# twopropmixtiny.net
KiCad netlist of a schematic drawn in EAGLE
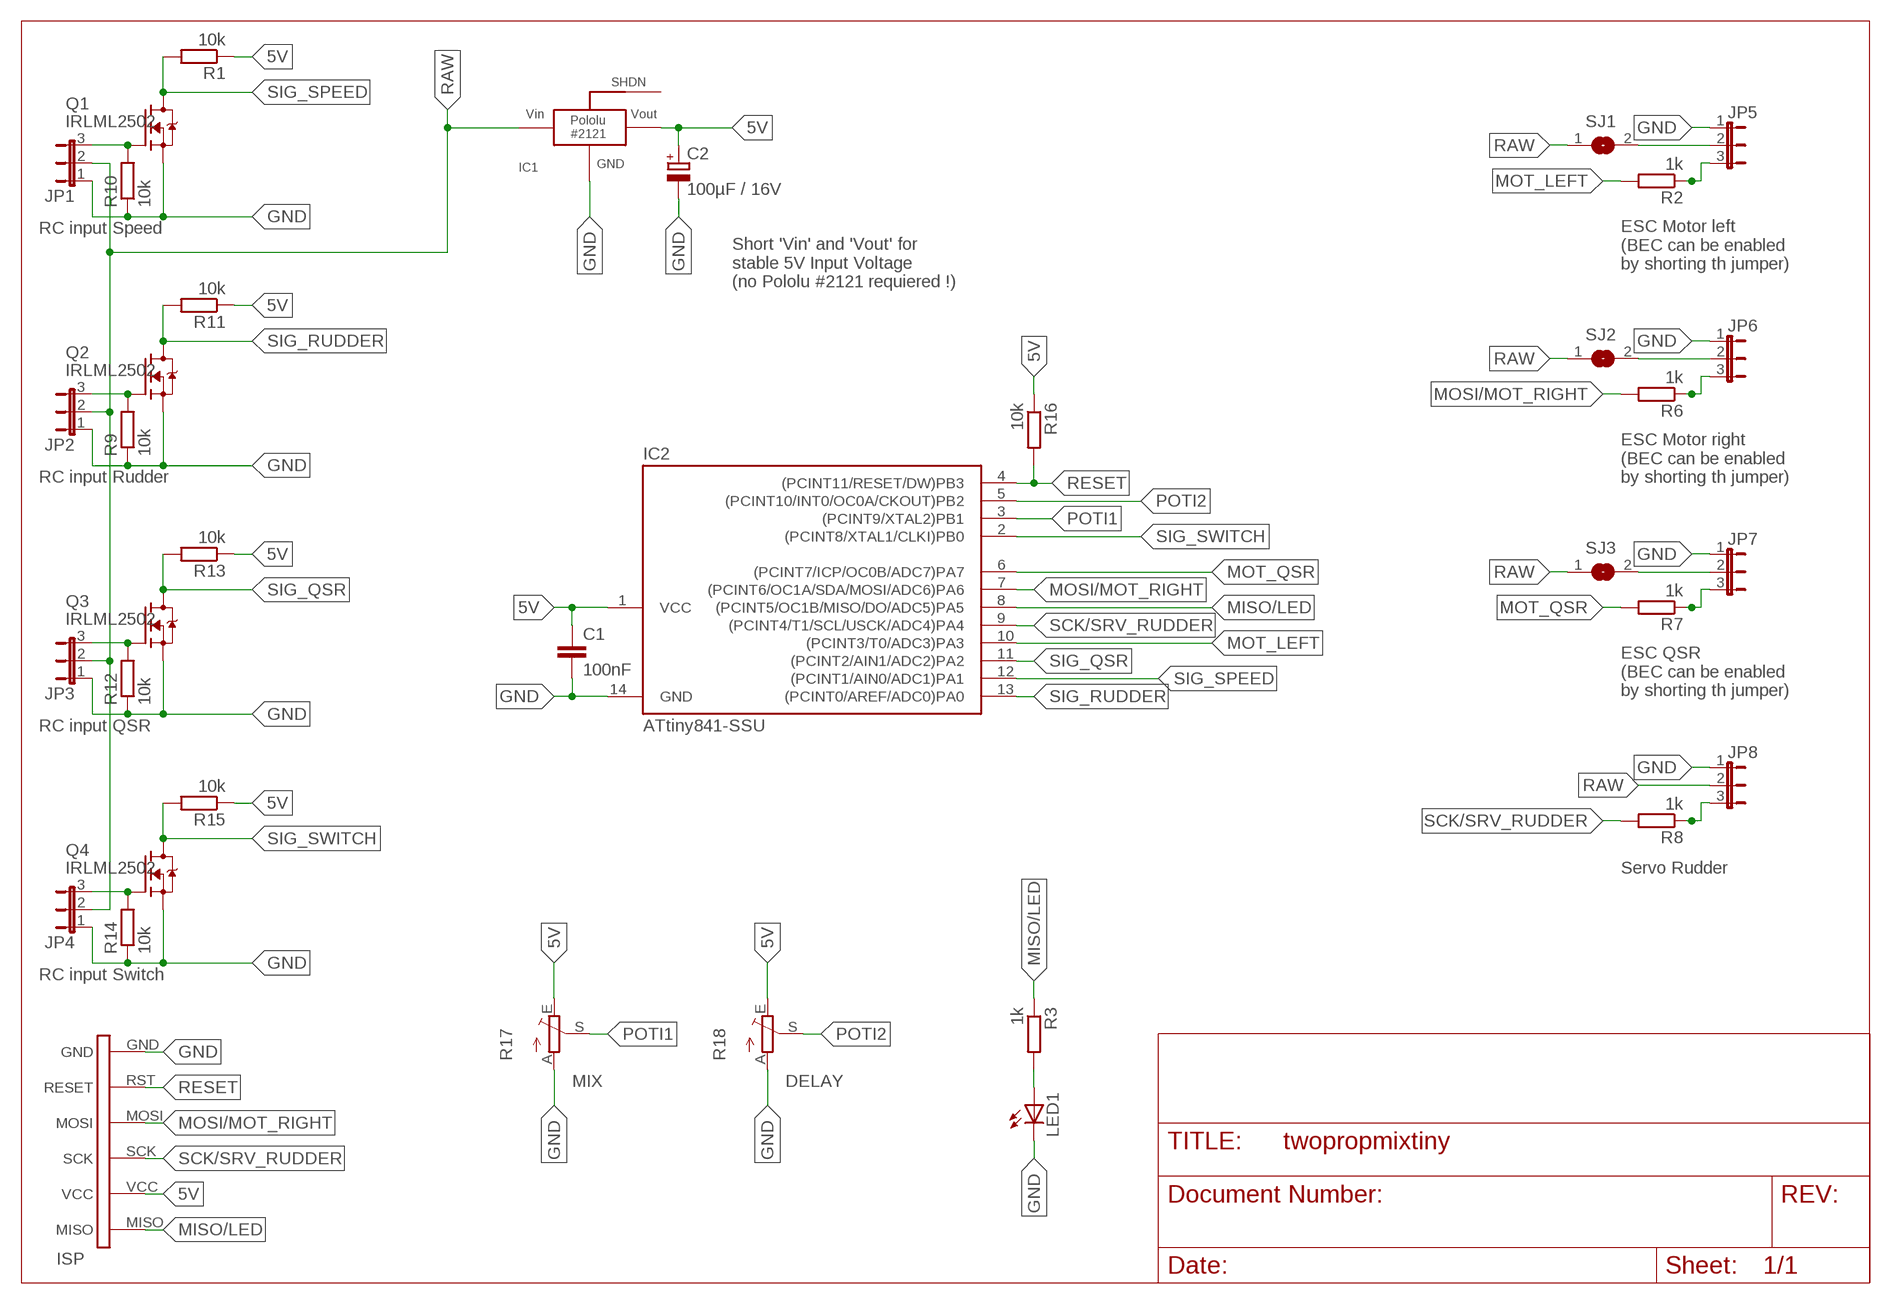
[diagram p0: schematic, sheet 1]

(export (version "E")
  (design (tool "Eeschema 10.0.6"))
  (components
    (comp (ref "C1")
      (value "100nF")
      (footprint "eagle-import:C0805")
      (libsource (lib "eagle-import") (part "C-EUC0805"))
    )
    (comp (ref "C2")
      (value "100µF / 16V")
      (footprint "eagle-import:PANASONIC_D")
      (libsource (lib "eagle-import") (part "CPOL-EUD"))
    )
    (comp (ref "IC1")
      (value "POLOLU2121")
      (footprint "eagle-import:POLOLU2121")
      (libsource (lib "eagle-import") (part "POLOLU2121"))
    )
    (comp (ref "IC2")
      (value "ATtiny841-SSU")
      (footprint "eagle-import:SOIC14")
      (libsource (lib "eagle-import") (part "TINY24/44/84-SSU"))
    )
    (comp (ref "JP1")
      (value "JP2EJP2_OHNE_TEXT")
      (footprint "eagle-import:JP2")
      (libsource (lib "eagle-import") (part "JP2EJP2_OHNE_TEXT"))
    )
    (comp (ref "JP2")
      (value "JP2EJP2_OHNE_TEXT")
      (footprint "eagle-import:JP2")
      (libsource (lib "eagle-import") (part "JP2EJP2_OHNE_TEXT"))
    )
    (comp (ref "JP3")
      (value "JP2EJP2_OHNE_TEXT")
      (footprint "eagle-import:JP2")
      (libsource (lib "eagle-import") (part "JP2EJP2_OHNE_TEXT"))
    )
    (comp (ref "JP4")
      (value "JP2EJP2_OHNE_TEXT")
      (footprint "eagle-import:JP2")
      (libsource (lib "eagle-import") (part "JP2EJP2_OHNE_TEXT"))
    )
    (comp (ref "JP5")
      (value "JP2EJP2_OHNE_TEXT")
      (footprint "eagle-import:JP2")
      (libsource (lib "eagle-import") (part "JP2EJP2_OHNE_TEXT"))
    )
    (comp (ref "JP6")
      (value "JP2EJP2_OHNE_TEXT")
      (footprint "eagle-import:JP2")
      (libsource (lib "eagle-import") (part "JP2EJP2_OHNE_TEXT"))
    )
    (comp (ref "JP7")
      (value "JP2EJP2_OHNE_TEXT")
      (footprint "eagle-import:JP2")
      (libsource (lib "eagle-import") (part "JP2EJP2_OHNE_TEXT"))
    )
    (comp (ref "JP8")
      (value "JP2EJP2_OHNE_TEXT")
      (footprint "eagle-import:JP2")
      (libsource (lib "eagle-import") (part "JP2EJP2_OHNE_TEXT"))
    )
    (comp (ref "LED1")
      (value "LEDCHIPLED_0805")
      (footprint "eagle-import:CHIPLED_0805")
      (libsource (lib "eagle-import") (part "LEDCHIPLED_0805"))
    )
    (comp (ref "Q1")
      (value "IRLML2502")
      (footprint "eagle-import:SOT23-3")
      (libsource (lib "eagle-import") (part "IRLML2502"))
    )
    (comp (ref "Q2")
      (value "IRLML2502")
      (footprint "eagle-import:SOT23-3")
      (libsource (lib "eagle-import") (part "IRLML2502"))
    )
    (comp (ref "Q3")
      (value "IRLML2502")
      (footprint "eagle-import:SOT23-3")
      (libsource (lib "eagle-import") (part "IRLML2502"))
    )
    (comp (ref "Q4")
      (value "IRLML2502")
      (footprint "eagle-import:SOT23-3")
      (libsource (lib "eagle-import") (part "IRLML2502"))
    )
    (comp (ref "R1")
      (value "10k")
      (footprint "eagle-import:R0805")
      (libsource (lib "eagle-import") (part "R-EU_R0805"))
    )
    (comp (ref "R2")
      (value "1k")
      (footprint "eagle-import:R0805")
      (libsource (lib "eagle-import") (part "R-EU_R0805"))
    )
    (comp (ref "R3")
      (value "1k")
      (footprint "eagle-import:R0805")
      (libsource (lib "eagle-import") (part "R-EU_R0805"))
    )
    (comp (ref "R6")
      (value "1k")
      (footprint "eagle-import:R0805")
      (libsource (lib "eagle-import") (part "R-EU_R0805"))
    )
    (comp (ref "R7")
      (value "1k")
      (footprint "eagle-import:R0805")
      (libsource (lib "eagle-import") (part "R-EU_R0805"))
    )
    (comp (ref "R8")
      (value "1k")
      (footprint "eagle-import:R0805")
      (libsource (lib "eagle-import") (part "R-EU_R0805"))
    )
    (comp (ref "R9")
      (value "10k")
      (footprint "eagle-import:R0805")
      (libsource (lib "eagle-import") (part "R-EU_R0805"))
    )
    (comp (ref "R10")
      (value "10k")
      (footprint "eagle-import:R0805")
      (libsource (lib "eagle-import") (part "R-EU_R0805"))
    )
    (comp (ref "R11")
      (value "10k")
      (footprint "eagle-import:R0805")
      (libsource (lib "eagle-import") (part "R-EU_R0805"))
    )
    (comp (ref "R12")
      (value "10k")
      (footprint "eagle-import:R0805")
      (libsource (lib "eagle-import") (part "R-EU_R0805"))
    )
    (comp (ref "R13")
      (value "10k")
      (footprint "eagle-import:R0805")
      (libsource (lib "eagle-import") (part "R-EU_R0805"))
    )
    (comp (ref "R14")
      (value "10k")
      (footprint "eagle-import:R0805")
      (libsource (lib "eagle-import") (part "R-EU_R0805"))
    )
    (comp (ref "R15")
      (value "10k")
      (footprint "eagle-import:R0805")
      (libsource (lib "eagle-import") (part "R-EU_R0805"))
    )
    (comp (ref "R16")
      (value "10k")
      (footprint "eagle-import:R0805")
      (libsource (lib "eagle-import") (part "R-EU_R0805"))
    )
    (comp (ref "R17")
      (value "TRIM_EU-PT10")
      (footprint "eagle-import:PT-10")
      (libsource (lib "eagle-import") (part "TRIM_EU-PT10"))
    )
    (comp (ref "R18")
      (value "TRIM_EU-PT10")
      (footprint "eagle-import:PT-10")
      (libsource (lib "eagle-import") (part "TRIM_EU-PT10"))
    )
    (comp (ref "SJ1") (value "SJ") (footprint "eagle-import:SJ") (libsource (lib "eagle-import") (part "SJ")))
    (comp (ref "SJ2") (value "SJ") (footprint "eagle-import:SJ") (libsource (lib "eagle-import") (part "SJ")))
    (comp (ref "SJ3") (value "SJ") (footprint "eagle-import:SJ") (libsource (lib "eagle-import") (part "SJ")))
    (comp (ref "U$1")
      (value "ISP")
      (footprint "eagle-import:ISP")
      (libsource (lib "eagle-import") (part "ISP"))
    )
  )
  (nets
    (net (code "1") (name "5V") (class "Default")
      (node (ref "C1") (pin "1") (pinfunction "1_1") (pintype "passive"))
      (node (ref "C2") (pin "+") (pinfunction "+_+") (pintype "passive"))
      (node (ref "IC1") (pin "VOUT") (pinfunction "VOUT_VOUT") (pintype "bidirectional"))
      (node (ref "IC2") (pin "1") (pinfunction "VCC_1") (pintype "power_in"))
      (node (ref "R1") (pin "1") (pinfunction "1_1") (pintype "passive"))
      (node (ref "R11") (pin "1") (pinfunction "1_1") (pintype "passive"))
      (node (ref "R13") (pin "1") (pinfunction "1_1") (pintype "passive"))
      (node (ref "R15") (pin "1") (pinfunction "1_1") (pintype "passive"))
      (node (ref "R16") (pin "1") (pinfunction "1_1") (pintype "passive"))
      (node (ref "R17") (pin "E") (pinfunction "E_E") (pintype "passive"))
      (node (ref "R18") (pin "E") (pinfunction "E_E") (pintype "passive"))
      (node (ref "U$1") (pin "VCC") (pinfunction "VCC_VCC") (pintype "bidirectional"))
    )
    (net (code "2") (name "GND") (class "Default")
      (node (ref "C1") (pin "2") (pinfunction "2_2") (pintype "passive"))
      (node (ref "C2") (pin "-") (pinfunction "-_-") (pintype "passive"))
      (node (ref "IC1") (pin "GND") (pinfunction "GND_GND") (pintype "bidirectional"))
      (node (ref "IC2") (pin "14") (pinfunction "GND_14") (pintype "power_in"))
      (node (ref "JP1") (pin "1") (pinfunction "1_1") (pintype "passive"))
      (node (ref "JP2") (pin "1") (pinfunction "1_1") (pintype "passive"))
      (node (ref "JP3") (pin "1") (pinfunction "1_1") (pintype "passive"))
      (node (ref "JP4") (pin "1") (pinfunction "1_1") (pintype "passive"))
      (node (ref "JP5") (pin "1") (pinfunction "1_1") (pintype "passive"))
      (node (ref "JP6") (pin "1") (pinfunction "1_1") (pintype "passive"))
      (node (ref "JP7") (pin "1") (pinfunction "1_1") (pintype "passive"))
      (node (ref "JP8") (pin "1") (pinfunction "1_1") (pintype "passive"))
      (node (ref "LED1") (pin "C") (pinfunction "C_C") (pintype "passive"))
      (node (ref "Q1") (pin "2") (pinfunction "S_2") (pintype "passive"))
      (node (ref "Q2") (pin "2") (pinfunction "S_2") (pintype "passive"))
      (node (ref "Q3") (pin "2") (pinfunction "S_2") (pintype "passive"))
      (node (ref "Q4") (pin "2") (pinfunction "S_2") (pintype "passive"))
      (node (ref "R10") (pin "1") (pinfunction "1_1") (pintype "passive"))
      (node (ref "R12") (pin "1") (pinfunction "1_1") (pintype "passive"))
      (node (ref "R14") (pin "1") (pinfunction "1_1") (pintype "passive"))
      (node (ref "R17") (pin "A") (pinfunction "A_A") (pintype "passive"))
      (node (ref "R18") (pin "A") (pinfunction "A_A") (pintype "passive"))
      (node (ref "R9") (pin "1") (pinfunction "1_1") (pintype "passive"))
      (node (ref "U$1") (pin "GND") (pinfunction "GND_GND") (pintype "bidirectional"))
    )
    (net (code "3") (name "MISO{slash}LED") (class "Default")
      (node (ref "IC2") (pin "8") (pinfunction "(PCINT5/OC1B/MISO/DO/ADC5)PA5_8") (pintype "bidirectional"))
      (node (ref "R3") (pin "1") (pinfunction "1_1") (pintype "passive"))
      (node (ref "U$1") (pin "MISO") (pinfunction "MISO_MISO") (pintype "bidirectional"))
    )
    (net (code "4") (name "MOSI{slash}MOT_RIGHT") (class "Default")
      (node (ref "IC2") (pin "7") (pinfunction "(PCINT6/OC1A/SDA/MOSI/ADC6)PA6_7") (pintype "bidirectional"))
      (node (ref "R6") (pin "2") (pinfunction "2_2") (pintype "passive"))
      (node (ref "U$1") (pin "MOSI") (pinfunction "MOSI_MOSI") (pintype "bidirectional"))
    )
    (net (code "5") (name "MOT_LEFT") (class "Default")
      (node (ref "IC2") (pin "10") (pinfunction "(PCINT3/T0/ADC3)PA3_10") (pintype "bidirectional"))
      (node (ref "R2") (pin "2") (pinfunction "2_2") (pintype "passive"))
    )
    (net (code "6") (name "MOT_QSR") (class "Default")
      (node (ref "IC2") (pin "6") (pinfunction "(PCINT7/ICP/OC0B/ADC7)PA7_6") (pintype "bidirectional"))
      (node (ref "R7") (pin "2") (pinfunction "2_2") (pintype "passive"))
    )
    (net (code "7") (name "Net-(JP5-Pad2)") (class "Default")
      (node (ref "JP5") (pin "2") (pinfunction "2_2") (pintype "passive"))
      (node (ref "SJ1") (pin "2") (pinfunction "2_2") (pintype "passive"))
    )
    (net (code "8") (name "Net-(JP5-Pad3)") (class "Default")
      (node (ref "JP5") (pin "3") (pinfunction "3_3") (pintype "passive"))
      (node (ref "R2") (pin "1") (pinfunction "1_1") (pintype "passive"))
    )
    (net (code "9") (name "Net-(JP6-Pad2)") (class "Default")
      (node (ref "JP6") (pin "2") (pinfunction "2_2") (pintype "passive"))
      (node (ref "SJ2") (pin "2") (pinfunction "2_2") (pintype "passive"))
    )
    (net (code "10") (name "Net-(JP6-Pad3)") (class "Default")
      (node (ref "JP6") (pin "3") (pinfunction "3_3") (pintype "passive"))
      (node (ref "R6") (pin "1") (pinfunction "1_1") (pintype "passive"))
    )
    (net (code "11") (name "Net-(JP7-Pad2)") (class "Default")
      (node (ref "JP7") (pin "2") (pinfunction "2_2") (pintype "passive"))
      (node (ref "SJ3") (pin "2") (pinfunction "2_2") (pintype "passive"))
    )
    (net (code "12") (name "Net-(JP7-Pad3)") (class "Default")
      (node (ref "JP7") (pin "3") (pinfunction "3_3") (pintype "passive"))
      (node (ref "R7") (pin "1") (pinfunction "1_1") (pintype "passive"))
    )
    (net (code "13") (name "Net-(JP8-Pad3)") (class "Default")
      (node (ref "JP8") (pin "3") (pinfunction "3_3") (pintype "passive"))
      (node (ref "R8") (pin "1") (pinfunction "1_1") (pintype "passive"))
    )
    (net (code "14") (name "Net-(LED1-PadA)") (class "Default")
      (node (ref "LED1") (pin "A") (pinfunction "A_A") (pintype "passive"))
      (node (ref "R3") (pin "2") (pinfunction "2_2") (pintype "passive"))
    )
    (net (code "15") (name "Net-(Q1-G)") (class "Default")
      (node (ref "JP1") (pin "3") (pinfunction "3_3") (pintype "passive"))
      (node (ref "Q1") (pin "1") (pinfunction "G_1") (pintype "passive"))
      (node (ref "R10") (pin "2") (pinfunction "2_2") (pintype "passive"))
    )
    (net (code "16") (name "Net-(Q2-G)") (class "Default")
      (node (ref "JP2") (pin "3") (pinfunction "3_3") (pintype "passive"))
      (node (ref "Q2") (pin "1") (pinfunction "G_1") (pintype "passive"))
      (node (ref "R9") (pin "2") (pinfunction "2_2") (pintype "passive"))
    )
    (net (code "17") (name "Net-(Q3-G)") (class "Default")
      (node (ref "JP3") (pin "3") (pinfunction "3_3") (pintype "passive"))
      (node (ref "Q3") (pin "1") (pinfunction "G_1") (pintype "passive"))
      (node (ref "R12") (pin "2") (pinfunction "2_2") (pintype "passive"))
    )
    (net (code "18") (name "Net-(Q4-G)") (class "Default")
      (node (ref "JP4") (pin "3") (pinfunction "3_3") (pintype "passive"))
      (node (ref "Q4") (pin "1") (pinfunction "G_1") (pintype "passive"))
      (node (ref "R14") (pin "2") (pinfunction "2_2") (pintype "passive"))
    )
    (net (code "19") (name "POTI1") (class "Default")
      (node (ref "IC2") (pin "3") (pinfunction "(PCINT9/XTAL2)PB1_3") (pintype "bidirectional"))
      (node (ref "R17") (pin "S") (pinfunction "S_S") (pintype "passive"))
    )
    (net (code "20") (name "POTI2") (class "Default")
      (node (ref "IC2") (pin "5") (pinfunction "(PCINT10/INT0/OC0A/CKOUT)PB2_5") (pintype "bidirectional"))
      (node (ref "R18") (pin "S") (pinfunction "S_S") (pintype "passive"))
    )
    (net (code "21") (name "RAW") (class "Default")
      (node (ref "IC1") (pin "VIN") (pinfunction "VIN_VIN") (pintype "bidirectional"))
      (node (ref "JP1") (pin "2") (pinfunction "2_2") (pintype "passive"))
      (node (ref "JP2") (pin "2") (pinfunction "2_2") (pintype "passive"))
      (node (ref "JP3") (pin "2") (pinfunction "2_2") (pintype "passive"))
      (node (ref "JP4") (pin "2") (pinfunction "2_2") (pintype "passive"))
      (node (ref "JP8") (pin "2") (pinfunction "2_2") (pintype "passive"))
      (node (ref "SJ1") (pin "1") (pinfunction "1_1") (pintype "passive"))
      (node (ref "SJ2") (pin "1") (pinfunction "1_1") (pintype "passive"))
      (node (ref "SJ3") (pin "1") (pinfunction "1_1") (pintype "passive"))
    )
    (net (code "22") (name "RESET") (class "Default")
      (node (ref "IC2") (pin "4") (pinfunction "(PCINT11/RESET/DW)PB3_4") (pintype "bidirectional"))
      (node (ref "R16") (pin "2") (pinfunction "2_2") (pintype "passive"))
      (node (ref "U$1") (pin "RST") (pinfunction "RESET_RST") (pintype "bidirectional"))
    )
    (net (code "23") (name "SCK{slash}SRV_RUDDER") (class "Default")
      (node (ref "IC2") (pin "9") (pinfunction "(PCINT4/T1/SCL/USCK/ADC4)PA4_9") (pintype "bidirectional"))
      (node (ref "R8") (pin "2") (pinfunction "2_2") (pintype "passive"))
      (node (ref "U$1") (pin "SCK") (pinfunction "SCK_SCK") (pintype "bidirectional"))
    )
    (net (code "24") (name "SIG_QSR") (class "Default")
      (node (ref "IC2") (pin "11") (pinfunction "(PCINT2/AIN1/ADC2)PA2_11") (pintype "bidirectional"))
      (node (ref "Q3") (pin "3") (pinfunction "D_3") (pintype "passive"))
      (node (ref "R13") (pin "2") (pinfunction "2_2") (pintype "passive"))
    )
    (net (code "25") (name "SIG_RUDDER") (class "Default")
      (node (ref "IC2") (pin "13") (pinfunction "(PCINT0/AREF/ADC0)PA0_13") (pintype "bidirectional"))
      (node (ref "Q2") (pin "3") (pinfunction "D_3") (pintype "passive"))
      (node (ref "R11") (pin "2") (pinfunction "2_2") (pintype "passive"))
    )
    (net (code "26") (name "SIG_SPEED") (class "Default")
      (node (ref "IC2") (pin "12") (pinfunction "(PCINT1/AIN0/ADC1)PA1_12") (pintype "bidirectional"))
      (node (ref "Q1") (pin "3") (pinfunction "D_3") (pintype "passive"))
      (node (ref "R1") (pin "2") (pinfunction "2_2") (pintype "passive"))
    )
    (net (code "27") (name "SIG_SWITCH") (class "Default")
      (node (ref "IC2") (pin "2") (pinfunction "(PCINT8/XTAL1/CLKI)PB0_2") (pintype "bidirectional"))
      (node (ref "Q4") (pin "3") (pinfunction "D_3") (pintype "passive"))
      (node (ref "R15") (pin "2") (pinfunction "2_2") (pintype "passive"))
    )
    (net (code "28") (name "unconnected-(IC1-PadSHDN)") (class "Default")
      (node (ref "IC1") (pin "SHDN") (pinfunction "SHDN_SHDN") (pintype "bidirectional"))
    )
  )
)
